# Sensor_LinearCCD.net
KiCad netlist of a schematic drawn in EAGLE
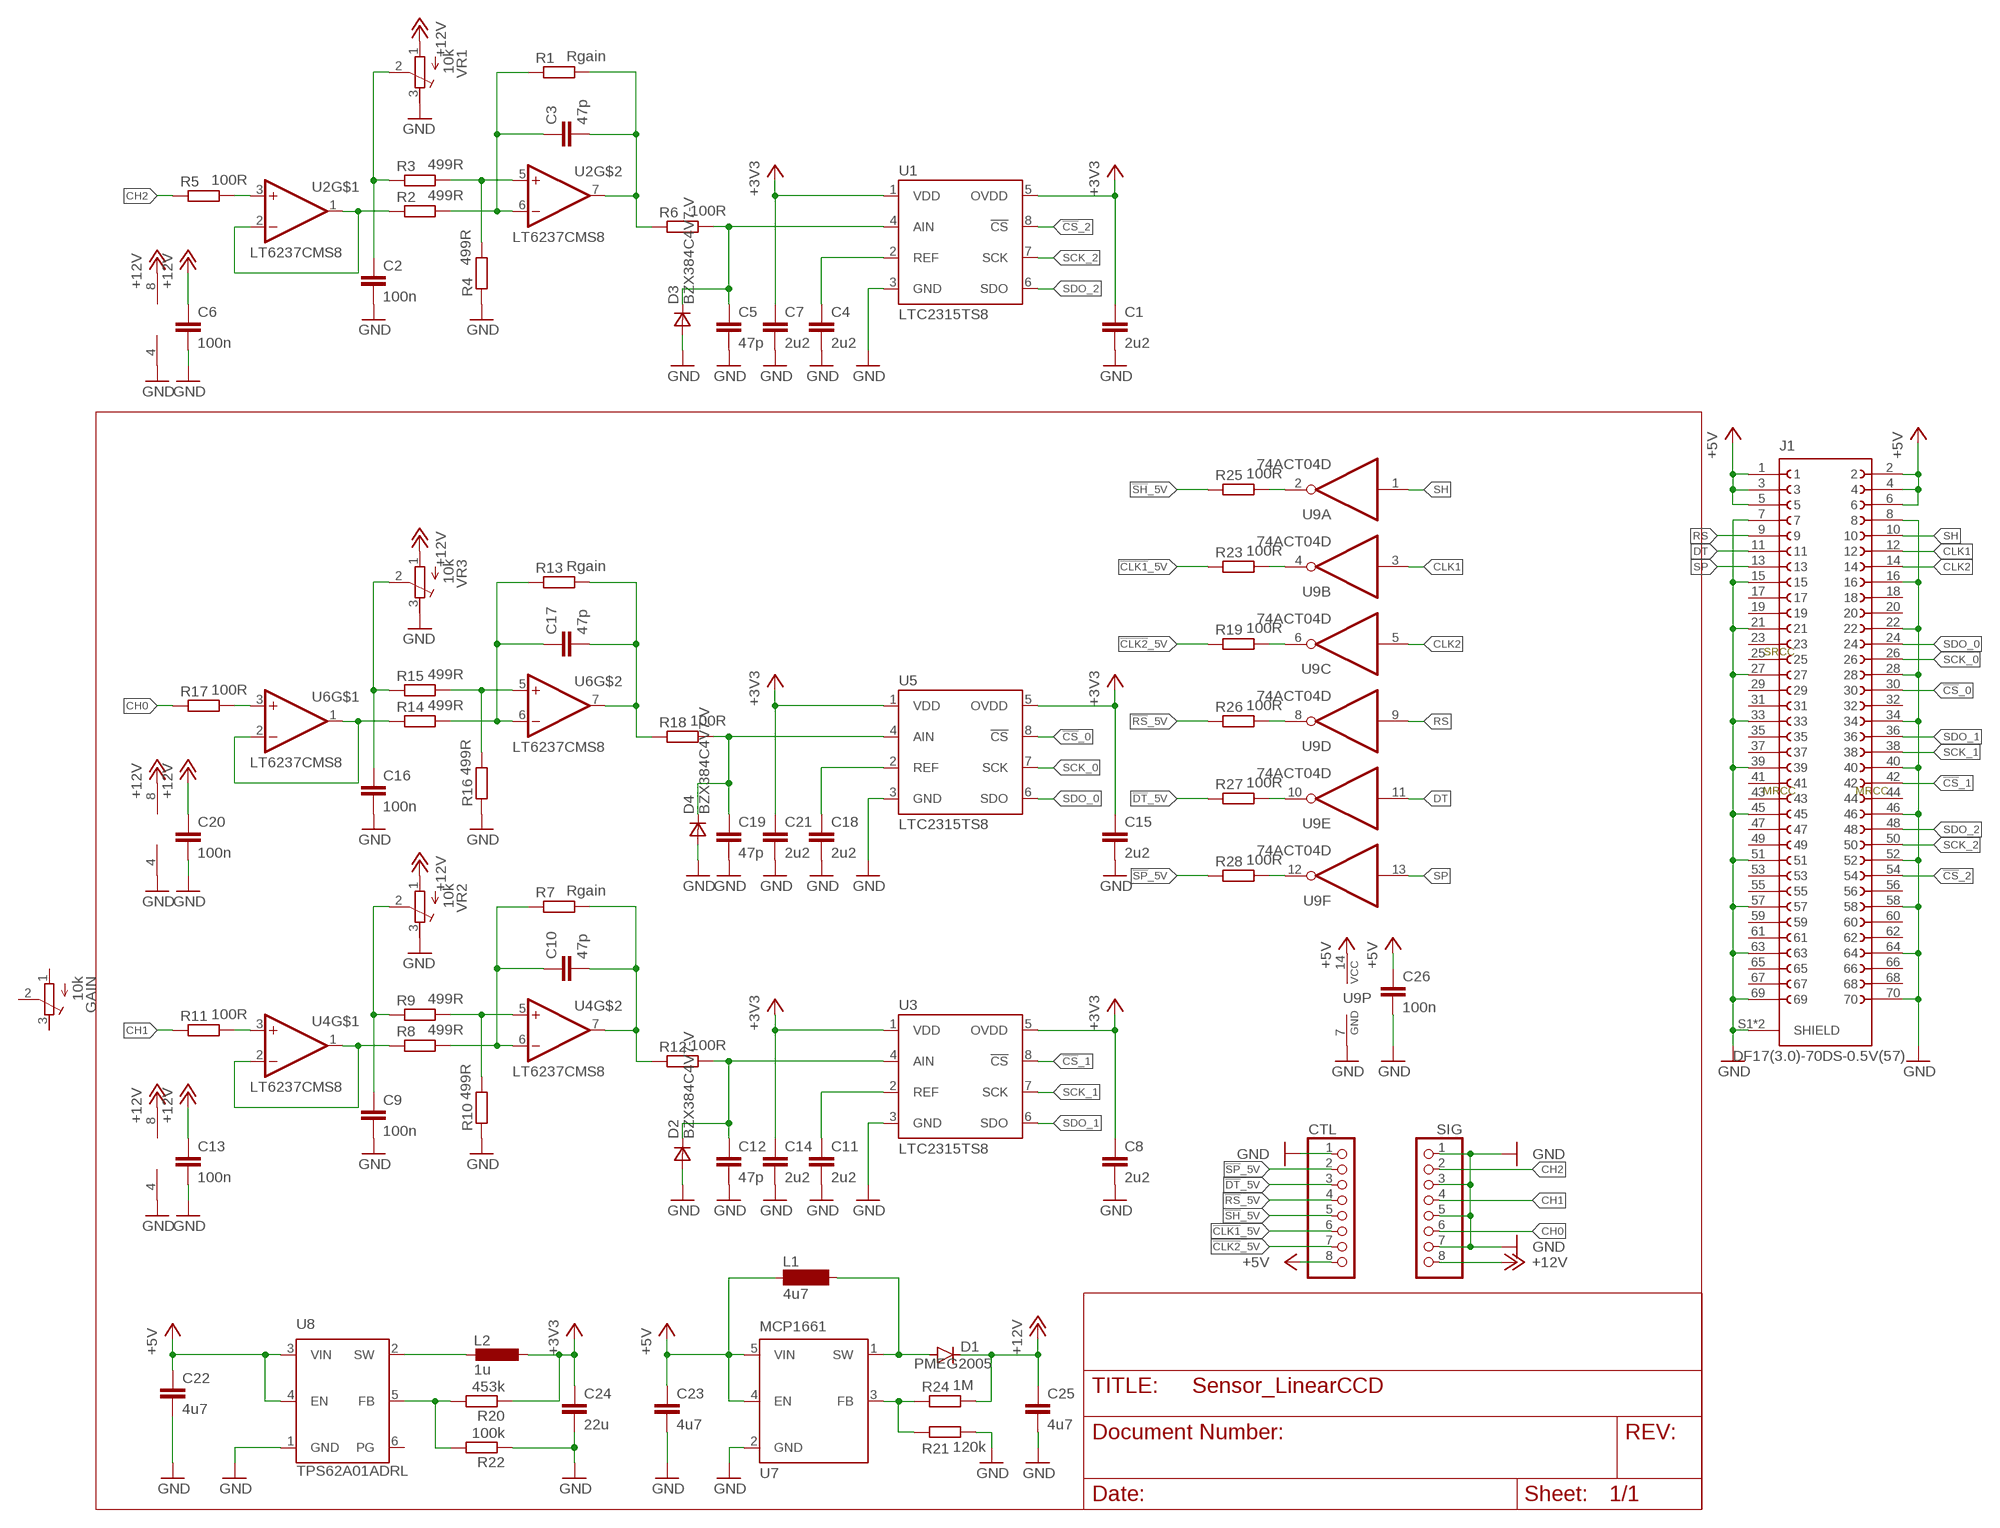
[diagram p0: schematic, sheet 1]

(export (version "E")
  (design (tool "Eeschema 10.0.6"))
  (components
    (comp (ref "C1")
      (value "2u2")
      (footprint "eagle-import:C0603")
      (libsource (lib "eagle-import") (part "C-EUC0603"))
    )
    (comp (ref "C2")
      (value "100n")
      (footprint "eagle-import:C0402")
      (libsource (lib "eagle-import") (part "rcl_334_C-EUC0402"))
    )
    (comp (ref "C3")
      (value "47p")
      (footprint "eagle-import:C0402")
      (libsource (lib "eagle-import") (part "rcl_334_C-EUC0402"))
    )
    (comp (ref "C4")
      (value "2u2")
      (footprint "eagle-import:C0603")
      (libsource (lib "eagle-import") (part "C-EUC0603"))
    )
    (comp (ref "C5")
      (value "47p")
      (footprint "eagle-import:C0402")
      (libsource (lib "eagle-import") (part "rcl_334_C-EUC0402"))
    )
    (comp (ref "C6")
      (value "100n")
      (footprint "eagle-import:C0402")
      (libsource (lib "eagle-import") (part "rcl_334_C-EUC0402"))
    )
    (comp (ref "C7")
      (value "2u2")
      (footprint "eagle-import:C0603")
      (libsource (lib "eagle-import") (part "C-EUC0603"))
    )
    (comp (ref "C8")
      (value "2u2")
      (footprint "eagle-import:C0603")
      (libsource (lib "eagle-import") (part "C-EUC0603"))
    )
    (comp (ref "C9")
      (value "100n")
      (footprint "eagle-import:C0402")
      (libsource (lib "eagle-import") (part "rcl_334_C-EUC0402"))
    )
    (comp (ref "C10")
      (value "47p")
      (footprint "eagle-import:C0402")
      (libsource (lib "eagle-import") (part "rcl_334_C-EUC0402"))
    )
    (comp (ref "C11")
      (value "2u2")
      (footprint "eagle-import:C0603")
      (libsource (lib "eagle-import") (part "C-EUC0603"))
    )
    (comp (ref "C12")
      (value "47p")
      (footprint "eagle-import:C0402")
      (libsource (lib "eagle-import") (part "rcl_334_C-EUC0402"))
    )
    (comp (ref "C13")
      (value "100n")
      (footprint "eagle-import:C0402")
      (libsource (lib "eagle-import") (part "rcl_334_C-EUC0402"))
    )
    (comp (ref "C14")
      (value "2u2")
      (footprint "eagle-import:C0603")
      (libsource (lib "eagle-import") (part "C-EUC0603"))
    )
    (comp (ref "C15")
      (value "2u2")
      (footprint "eagle-import:C0603")
      (libsource (lib "eagle-import") (part "C-EUC0603"))
    )
    (comp (ref "C16")
      (value "100n")
      (footprint "eagle-import:C0402")
      (libsource (lib "eagle-import") (part "rcl_334_C-EUC0402"))
    )
    (comp (ref "C17")
      (value "47p")
      (footprint "eagle-import:C0402")
      (libsource (lib "eagle-import") (part "rcl_334_C-EUC0402"))
    )
    (comp (ref "C18")
      (value "2u2")
      (footprint "eagle-import:C0603")
      (libsource (lib "eagle-import") (part "C-EUC0603"))
    )
    (comp (ref "C19")
      (value "47p")
      (footprint "eagle-import:C0402")
      (libsource (lib "eagle-import") (part "rcl_334_C-EUC0402"))
    )
    (comp (ref "C20")
      (value "100n")
      (footprint "eagle-import:C0402")
      (libsource (lib "eagle-import") (part "rcl_334_C-EUC0402"))
    )
    (comp (ref "C21")
      (value "2u2")
      (footprint "eagle-import:C0603")
      (libsource (lib "eagle-import") (part "C-EUC0603"))
    )
    (comp (ref "C22")
      (value "4u7")
      (footprint "eagle-import:C0603")
      (libsource (lib "eagle-import") (part "C-EUC0603"))
    )
    (comp (ref "C23")
      (value "4u7")
      (footprint "eagle-import:C0603")
      (libsource (lib "eagle-import") (part "C-EUC0603"))
    )
    (comp (ref "C24")
      (value "22u")
      (footprint "eagle-import:C0603")
      (libsource (lib "eagle-import") (part "C-EUC0603"))
    )
    (comp (ref "C25")
      (value "4u7")
      (footprint "eagle-import:C0603")
      (libsource (lib "eagle-import") (part "C-EUC0603"))
    )
    (comp (ref "C26")
      (value "100n")
      (footprint "eagle-import:C0402")
      (libsource (lib "eagle-import") (part "rcl_334_C-EUC0402"))
    )
    (comp (ref "CTL")
      (value "PINHD-1X8_2.00")
      (footprint "eagle-import:1X08M")
      (libsource (lib "eagle-import") (part "PINHD-1X8_2.00"))
    )
    (comp (ref "D1")
      (value "PMEG2005")
      (footprint "eagle-import:SOD123")
      (libsource (lib "eagle-import") (part "DIODE-SOD123"))
    )
    (comp (ref "D2")
      (value "BZX384C4V7-V")
      (footprint "eagle-import:SOD323")
      (fields (field (name "MPN") "CDSOD323-T05C"))
      (libsource (lib "eagle-import") (part "DSOD323"))
    )
    (comp (ref "D3")
      (value "BZX384C4V7-V")
      (footprint "eagle-import:SOD323")
      (fields (field (name "MPN") "CDSOD323-T05C"))
      (libsource (lib "eagle-import") (part "DSOD323"))
    )
    (comp (ref "D4")
      (value "BZX384C4V7-V")
      (footprint "eagle-import:SOD323")
      (fields (field (name "MPN") "CDSOD323-T05C"))
      (libsource (lib "eagle-import") (part "DSOD323"))
    )
    (comp (ref "GAIN")
      (value "10k")
      (footprint "eagle-import:RTRIM3224J")
      (libsource (lib "eagle-import") (part "R-TRIMM3224J"))
    )
    (comp (ref "J1")
      (value "DF17(3.0)-70DS-0.5V(57)")
      (footprint "eagle-import:DF17(3.0)-70DS-0.5V(57)")
      (libsource (lib "eagle-import") (part "DF17(3.0)-70DS-0.5V(57)"))
    )
    (comp (ref "L1")
      (value "4u7")
      (footprint "eagle-import:L4012")
      (libsource (lib "eagle-import") (part "L4012"))
    )
    (comp (ref "L2")
      (value "1u")
      (footprint "eagle-import:L1008")
      (fields (field (name "MPN") "LQM2HPN1R0MG0L"))
      (libsource (lib "eagle-import") (part "L-EU1008"))
    )
    (comp (ref "R1")
      (value "Rgain")
      (footprint "eagle-import:R0402")
      (libsource (lib "eagle-import") (part "R-EU_R0402"))
    )
    (comp (ref "R2")
      (value "499R")
      (footprint "eagle-import:R0402")
      (libsource (lib "eagle-import") (part "R-EU_R0402"))
    )
    (comp (ref "R3")
      (value "499R")
      (footprint "eagle-import:R0402")
      (libsource (lib "eagle-import") (part "R-EU_R0402"))
    )
    (comp (ref "R4")
      (value "499R")
      (footprint "eagle-import:R0402")
      (libsource (lib "eagle-import") (part "R-EU_R0402"))
    )
    (comp (ref "R5")
      (value "100R")
      (footprint "eagle-import:R0402")
      (libsource (lib "eagle-import") (part "R-EU_R0402"))
    )
    (comp (ref "R6")
      (value "100R")
      (footprint "eagle-import:R0402")
      (libsource (lib "eagle-import") (part "R-EU_R0402"))
    )
    (comp (ref "R7")
      (value "Rgain")
      (footprint "eagle-import:R0402")
      (libsource (lib "eagle-import") (part "R-EU_R0402"))
    )
    (comp (ref "R8")
      (value "499R")
      (footprint "eagle-import:R0402")
      (libsource (lib "eagle-import") (part "R-EU_R0402"))
    )
    (comp (ref "R9")
      (value "499R")
      (footprint "eagle-import:R0402")
      (libsource (lib "eagle-import") (part "R-EU_R0402"))
    )
    (comp (ref "R10")
      (value "499R")
      (footprint "eagle-import:R0402")
      (libsource (lib "eagle-import") (part "R-EU_R0402"))
    )
    (comp (ref "R11")
      (value "100R")
      (footprint "eagle-import:R0402")
      (libsource (lib "eagle-import") (part "R-EU_R0402"))
    )
    (comp (ref "R12")
      (value "100R")
      (footprint "eagle-import:R0402")
      (libsource (lib "eagle-import") (part "R-EU_R0402"))
    )
    (comp (ref "R13")
      (value "Rgain")
      (footprint "eagle-import:R0402")
      (libsource (lib "eagle-import") (part "R-EU_R0402"))
    )
    (comp (ref "R14")
      (value "499R")
      (footprint "eagle-import:R0402")
      (libsource (lib "eagle-import") (part "R-EU_R0402"))
    )
    (comp (ref "R15")
      (value "499R")
      (footprint "eagle-import:R0402")
      (libsource (lib "eagle-import") (part "R-EU_R0402"))
    )
    (comp (ref "R16")
      (value "499R")
      (footprint "eagle-import:R0402")
      (libsource (lib "eagle-import") (part "R-EU_R0402"))
    )
    (comp (ref "R17")
      (value "100R")
      (footprint "eagle-import:R0402")
      (libsource (lib "eagle-import") (part "R-EU_R0402"))
    )
    (comp (ref "R18")
      (value "100R")
      (footprint "eagle-import:R0402")
      (libsource (lib "eagle-import") (part "R-EU_R0402"))
    )
    (comp (ref "R19")
      (value "100R")
      (footprint "eagle-import:R0402")
      (libsource (lib "eagle-import") (part "R-EU_R0402"))
    )
    (comp (ref "R20")
      (value "453k")
      (footprint "eagle-import:R0402")
      (libsource (lib "eagle-import") (part "R-EU_R0402"))
    )
    (comp (ref "R21")
      (value "120k")
      (footprint "eagle-import:R0402")
      (libsource (lib "eagle-import") (part "R-EU_R0402"))
    )
    (comp (ref "R22")
      (value "100k")
      (footprint "eagle-import:R0402")
      (libsource (lib "eagle-import") (part "R-EU_R0402"))
    )
    (comp (ref "R23")
      (value "100R")
      (footprint "eagle-import:R0402")
      (libsource (lib "eagle-import") (part "R-EU_R0402"))
    )
    (comp (ref "R24")
      (value "1M")
      (footprint "eagle-import:R0402")
      (libsource (lib "eagle-import") (part "R-EU_R0402"))
    )
    (comp (ref "R25")
      (value "100R")
      (footprint "eagle-import:R0402")
      (libsource (lib "eagle-import") (part "R-EU_R0402"))
    )
    (comp (ref "R26")
      (value "100R")
      (footprint "eagle-import:R0402")
      (libsource (lib "eagle-import") (part "R-EU_R0402"))
    )
    (comp (ref "R27")
      (value "100R")
      (footprint "eagle-import:R0402")
      (libsource (lib "eagle-import") (part "R-EU_R0402"))
    )
    (comp (ref "R28")
      (value "100R")
      (footprint "eagle-import:R0402")
      (libsource (lib "eagle-import") (part "R-EU_R0402"))
    )
    (comp (ref "SIG")
      (value "PINHD-1X8_2.00")
      (footprint "eagle-import:1X08M")
      (libsource (lib "eagle-import") (part "PINHD-1X8_2.00"))
    )
    (comp (ref "U1")
      (value "LTC2315TS8")
      (footprint "eagle-import:SOT23-8L")
      (libsource (lib "eagle-import") (part "LTC2315TS8"))
    )
    (comp (ref "U2")
      (value "LT6237CMS8")
      (footprint "eagle-import:MSOP08")
      (libsource (lib "eagle-import") (part "LT6237CMS8"))
    )
    (comp (ref "U3")
      (value "LTC2315TS8")
      (footprint "eagle-import:SOT23-8L")
      (libsource (lib "eagle-import") (part "LTC2315TS8"))
    )
    (comp (ref "U4")
      (value "LT6237CMS8")
      (footprint "eagle-import:MSOP08")
      (libsource (lib "eagle-import") (part "LT6237CMS8"))
    )
    (comp (ref "U5")
      (value "LTC2315TS8")
      (footprint "eagle-import:SOT23-8L")
      (libsource (lib "eagle-import") (part "LTC2315TS8"))
    )
    (comp (ref "U6")
      (value "LT6237CMS8")
      (footprint "eagle-import:MSOP08")
      (libsource (lib "eagle-import") (part "LT6237CMS8"))
    )
    (comp (ref "U7")
      (value "MCP1661")
      (footprint "eagle-import:SOT23-5L")
      (libsource (lib "eagle-import") (part "MCP1661"))
    )
    (comp (ref "U8")
      (value "TPS62A01ADRL")
      (footprint "eagle-import:SOTFL50P160X60-6N")
      (fields (field (name "MANUFACTURER_PART_NUMBER") "TPS62A01ADRLR"))
      (libsource (lib "eagle-import") (part "TPS62A01ADRL"))
    )
    (comp (ref "U9")
      (value "74ACT04D")
      (footprint "eagle-import:SO14")
      (libsource (lib "eagle-import") (part "7404DACT"))
    )
    (comp (ref "VR1")
      (value "10k")
      (footprint "eagle-import:RTRIM3224J")
      (libsource (lib "eagle-import") (part "R-TRIMM3224J"))
    )
    (comp (ref "VR2")
      (value "10k")
      (footprint "eagle-import:RTRIM3224J")
      (libsource (lib "eagle-import") (part "R-TRIMM3224J"))
    )
    (comp (ref "VR3")
      (value "10k")
      (footprint "eagle-import:RTRIM3224J")
      (libsource (lib "eagle-import") (part "R-TRIMM3224J"))
    )
  )
  (nets
    (net (code "1") (name "+3V3") (class "Default")
      (node (ref "C1") (pin "1") (pinfunction "1_1") (pintype "passive"))
      (node (ref "C14") (pin "1") (pinfunction "1_1") (pintype "passive"))
      (node (ref "C15") (pin "1") (pinfunction "1_1") (pintype "passive"))
      (node (ref "C21") (pin "1") (pinfunction "1_1") (pintype "passive"))
      (node (ref "C24") (pin "1") (pinfunction "1_1") (pintype "passive"))
      (node (ref "C7") (pin "1") (pinfunction "1_1") (pintype "passive"))
      (node (ref "C8") (pin "1") (pinfunction "1_1") (pintype "passive"))
      (node (ref "L2") (pin "1") (pinfunction "1_1") (pintype "passive"))
      (node (ref "R20") (pin "1") (pinfunction "1_1") (pintype "passive"))
      (node (ref "U1") (pin "1") (pinfunction "VDD_1") (pintype "power_in"))
      (node (ref "U1") (pin "5") (pinfunction "OVDD_5") (pintype "power_in"))
      (node (ref "U3") (pin "1") (pinfunction "VDD_1") (pintype "power_in"))
      (node (ref "U3") (pin "5") (pinfunction "OVDD_5") (pintype "power_in"))
      (node (ref "U5") (pin "1") (pinfunction "VDD_1") (pintype "power_in"))
      (node (ref "U5") (pin "5") (pinfunction "OVDD_5") (pintype "power_in"))
    )
    (net (code "2") (name "+5V") (class "Default")
      (node (ref "C22") (pin "1") (pinfunction "1_1") (pintype "passive"))
      (node (ref "C23") (pin "1") (pinfunction "1_1") (pintype "passive"))
      (node (ref "C26") (pin "1") (pinfunction "1_1") (pintype "passive"))
      (node (ref "CTL") (pin "8") (pinfunction "8_8") (pintype "passive"))
      (node (ref "J1") (pin "1") (pinfunction "1_1") (pintype "passive"))
      (node (ref "J1") (pin "2") (pinfunction "2_2") (pintype "passive"))
      (node (ref "J1") (pin "3") (pinfunction "3_3") (pintype "passive"))
      (node (ref "J1") (pin "4") (pinfunction "4_4") (pintype "passive"))
      (node (ref "J1") (pin "5") (pinfunction "5_5") (pintype "passive"))
      (node (ref "J1") (pin "6") (pinfunction "6_6") (pintype "passive"))
      (node (ref "L1") (pin "1") (pinfunction "1_1") (pintype "passive"))
      (node (ref "U7") (pin "4") (pinfunction "EN_4") (pintype "input"))
      (node (ref "U7") (pin "5") (pinfunction "VIN_5") (pintype "power_in"))
      (node (ref "U8") (pin "3") (pinfunction "VIN_3") (pintype "bidirectional"))
      (node (ref "U8") (pin "4") (pinfunction "EN_4") (pintype "bidirectional"))
      (node (ref "U9") (pin "14") (pinfunction "VCC_14") (pintype "power_in"))
    )
    (net (code "3") (name "+12V") (class "Default")
      (node (ref "C13") (pin "1") (pinfunction "1_1") (pintype "passive"))
      (node (ref "C20") (pin "1") (pinfunction "1_1") (pintype "passive"))
      (node (ref "C25") (pin "1") (pinfunction "1_1") (pintype "passive"))
      (node (ref "C6") (pin "1") (pinfunction "1_1") (pintype "passive"))
      (node (ref "D1") (pin "C") (pinfunction "C_C") (pintype "passive"))
      (node (ref "R24") (pin "2") (pinfunction "2_2") (pintype "passive"))
      (node (ref "SIG") (pin "8") (pinfunction "8_8") (pintype "passive"))
      (node (ref "U2") (pin "8") (pinfunction "V+_8") (pintype "power_in"))
      (node (ref "U4") (pin "8") (pinfunction "V+_8") (pintype "power_in"))
      (node (ref "U6") (pin "8") (pinfunction "V+_8") (pintype "power_in"))
      (node (ref "VR1") (pin "1") (pinfunction "A_1") (pintype "passive"))
      (node (ref "VR2") (pin "1") (pinfunction "A_1") (pintype "passive"))
      (node (ref "VR3") (pin "1") (pinfunction "A_1") (pintype "passive"))
    )
    (net (code "4") (name "/~{CLK1}_5V") (class "Default")
      (node (ref "CTL") (pin "6") (pinfunction "6_6") (pintype "passive"))
      (node (ref "R23") (pin "1") (pinfunction "1_1") (pintype "passive"))
    )
    (net (code "5") (name "/~{CLK2}_5V") (class "Default")
      (node (ref "CTL") (pin "7") (pinfunction "7_7") (pintype "passive"))
      (node (ref "R19") (pin "1") (pinfunction "1_1") (pintype "passive"))
    )
    (net (code "6") (name "/~{CS}_0") (class "Default")
      (node (ref "J1") (pin "30") (pinfunction "30_30") (pintype "passive"))
      (node (ref "U5") (pin "8") (pinfunction "~{CS}_8") (pintype "input"))
    )
    (net (code "7") (name "/~{CS}_1") (class "Default")
      (node (ref "J1") (pin "42") (pinfunction "42_42") (pintype "passive"))
      (node (ref "U3") (pin "8") (pinfunction "~{CS}_8") (pintype "input"))
    )
    (net (code "8") (name "/~{CS}_2") (class "Default")
      (node (ref "J1") (pin "54") (pinfunction "54_54") (pintype "passive"))
      (node (ref "U1") (pin "8") (pinfunction "~{CS}_8") (pintype "input"))
    )
    (net (code "9") (name "/~{DT}_5V") (class "Default")
      (node (ref "CTL") (pin "3") (pinfunction "3_3") (pintype "passive"))
      (node (ref "R27") (pin "1") (pinfunction "1_1") (pintype "passive"))
    )
    (net (code "10") (name "/~{RS}_5V") (class "Default")
      (node (ref "CTL") (pin "4") (pinfunction "4_4") (pintype "passive"))
      (node (ref "R26") (pin "1") (pinfunction "1_1") (pintype "passive"))
    )
    (net (code "11") (name "/~{SH}_5V") (class "Default")
      (node (ref "CTL") (pin "5") (pinfunction "5_5") (pintype "passive"))
      (node (ref "R25") (pin "1") (pinfunction "1_1") (pintype "passive"))
    )
    (net (code "12") (name "/~{SP}_5V") (class "Default")
      (node (ref "CTL") (pin "2") (pinfunction "2_2") (pintype "passive"))
      (node (ref "R28") (pin "1") (pinfunction "1_1") (pintype "passive"))
    )
    (net (code "13") (name "CH0") (class "Default")
      (node (ref "R17") (pin "1") (pinfunction "1_1") (pintype "passive"))
      (node (ref "SIG") (pin "6") (pinfunction "6_6") (pintype "passive"))
    )
    (net (code "14") (name "CH1") (class "Default")
      (node (ref "R11") (pin "1") (pinfunction "1_1") (pintype "passive"))
      (node (ref "SIG") (pin "4") (pinfunction "4_4") (pintype "passive"))
    )
    (net (code "15") (name "CH2") (class "Default")
      (node (ref "R5") (pin "1") (pinfunction "1_1") (pintype "passive"))
      (node (ref "SIG") (pin "2") (pinfunction "2_2") (pintype "passive"))
    )
    (net (code "16") (name "CLK1") (class "Default")
      (node (ref "J1") (pin "12") (pinfunction "12_12") (pintype "passive"))
      (node (ref "U9") (pin "3") (pinfunction "I_3") (pintype "input"))
    )
    (net (code "17") (name "CLK2") (class "Default")
      (node (ref "J1") (pin "14") (pinfunction "14_14") (pintype "passive"))
      (node (ref "U9") (pin "5") (pinfunction "I_5") (pintype "input"))
    )
    (net (code "18") (name "DT") (class "Default")
      (node (ref "J1") (pin "11") (pinfunction "11_11") (pintype "passive"))
      (node (ref "U9") (pin "11") (pinfunction "I_11") (pintype "input"))
    )
    (net (code "19") (name "GND") (class "Default")
      (node (ref "C1") (pin "2") (pinfunction "2_2") (pintype "passive"))
      (node (ref "C11") (pin "2") (pinfunction "2_2") (pintype "passive"))
      (node (ref "C12") (pin "2") (pinfunction "2_2") (pintype "passive"))
      (node (ref "C13") (pin "2") (pinfunction "2_2") (pintype "passive"))
      (node (ref "C14") (pin "2") (pinfunction "2_2") (pintype "passive"))
      (node (ref "C15") (pin "2") (pinfunction "2_2") (pintype "passive"))
      (node (ref "C16") (pin "2") (pinfunction "2_2") (pintype "passive"))
      (node (ref "C18") (pin "2") (pinfunction "2_2") (pintype "passive"))
      (node (ref "C19") (pin "2") (pinfunction "2_2") (pintype "passive"))
      (node (ref "C2") (pin "2") (pinfunction "2_2") (pintype "passive"))
      (node (ref "C20") (pin "2") (pinfunction "2_2") (pintype "passive"))
      (node (ref "C21") (pin "2") (pinfunction "2_2") (pintype "passive"))
      (node (ref "C22") (pin "2") (pinfunction "2_2") (pintype "passive"))
      (node (ref "C23") (pin "2") (pinfunction "2_2") (pintype "passive"))
      (node (ref "C24") (pin "2") (pinfunction "2_2") (pintype "passive"))
      (node (ref "C25") (pin "2") (pinfunction "2_2") (pintype "passive"))
      (node (ref "C26") (pin "2") (pinfunction "2_2") (pintype "passive"))
      (node (ref "C4") (pin "2") (pinfunction "2_2") (pintype "passive"))
      (node (ref "C5") (pin "2") (pinfunction "2_2") (pintype "passive"))
      (node (ref "C6") (pin "2") (pinfunction "2_2") (pintype "passive"))
      (node (ref "C7") (pin "2") (pinfunction "2_2") (pintype "passive"))
      (node (ref "C8") (pin "2") (pinfunction "2_2") (pintype "passive"))
      (node (ref "C9") (pin "2") (pinfunction "2_2") (pintype "passive"))
      (node (ref "CTL") (pin "1") (pinfunction "1_1") (pintype "passive"))
      (node (ref "D2") (pin "2") (pinfunction "A_2") (pintype "passive"))
      (node (ref "D3") (pin "2") (pinfunction "A_2") (pintype "passive"))
      (node (ref "D4") (pin "2") (pinfunction "A_2") (pintype "passive"))
      (node (ref "J1") (pin "15") (pinfunction "15_15") (pintype "passive"))
      (node (ref "J1") (pin "16") (pinfunction "16_16") (pintype "passive"))
      (node (ref "J1") (pin "21") (pinfunction "21_21") (pintype "passive"))
      (node (ref "J1") (pin "22") (pinfunction "22_22") (pintype "passive"))
      (node (ref "J1") (pin "27") (pinfunction "27_27") (pintype "passive"))
      (node (ref "J1") (pin "28") (pinfunction "28_28") (pintype "passive"))
      (node (ref "J1") (pin "33") (pinfunction "33_33") (pintype "passive"))
      (node (ref "J1") (pin "34") (pinfunction "34_34") (pintype "passive"))
      (node (ref "J1") (pin "39") (pinfunction "39_39") (pintype "passive"))
      (node (ref "J1") (pin "40") (pinfunction "40_40") (pintype "passive"))
      (node (ref "J1") (pin "45") (pinfunction "45_45") (pintype "passive"))
      (node (ref "J1") (pin "46") (pinfunction "46_46") (pintype "passive"))
      (node (ref "J1") (pin "51") (pinfunction "51_51") (pintype "passive"))
      (node (ref "J1") (pin "52") (pinfunction "52_52") (pintype "passive"))
      (node (ref "J1") (pin "57") (pinfunction "57_57") (pintype "passive"))
      (node (ref "J1") (pin "58") (pinfunction "58_58") (pintype "passive"))
      (node (ref "J1") (pin "63") (pinfunction "63_63") (pintype "passive"))
      (node (ref "J1") (pin "64") (pinfunction "64_64") (pintype "passive"))
      (node (ref "J1") (pin "69") (pinfunction "69_69") (pintype "passive"))
      (node (ref "J1") (pin "7") (pinfunction "7_7") (pintype "passive"))
      (node (ref "J1") (pin "70") (pinfunction "70_70") (pintype "passive"))
      (node (ref "J1") (pin "8") (pinfunction "8_8") (pintype "passive"))
      (node (ref "J1") (pin "S1") (pinfunction "SHIELD_S1") (pintype "passive"))
      (node (ref "J1") (pin "S2") (pinfunction "SHIELD_S2") (pintype "passive"))
      (node (ref "R10") (pin "1") (pinfunction "1_1") (pintype "passive"))
      (node (ref "R16") (pin "1") (pinfunction "1_1") (pintype "passive"))
      (node (ref "R21") (pin "2") (pinfunction "2_2") (pintype "passive"))
      (node (ref "R22") (pin "1") (pinfunction "1_1") (pintype "passive"))
      (node (ref "R4") (pin "1") (pinfunction "1_1") (pintype "passive"))
      (node (ref "SIG") (pin "1") (pinfunction "1_1") (pintype "passive"))
      (node (ref "SIG") (pin "3") (pinfunction "3_3") (pintype "passive"))
      (node (ref "SIG") (pin "5") (pinfunction "5_5") (pintype "passive"))
      (node (ref "SIG") (pin "7") (pinfunction "7_7") (pintype "passive"))
      (node (ref "U1") (pin "3") (pinfunction "GND_3") (pintype "power_in"))
      (node (ref "U2") (pin "4") (pinfunction "V-_4") (pintype "power_in"))
      (node (ref "U3") (pin "3") (pinfunction "GND_3") (pintype "power_in"))
      (node (ref "U4") (pin "4") (pinfunction "V-_4") (pintype "power_in"))
      (node (ref "U5") (pin "3") (pinfunction "GND_3") (pintype "power_in"))
      (node (ref "U6") (pin "4") (pinfunction "V-_4") (pintype "power_in"))
      (node (ref "U7") (pin "2") (pinfunction "GND_2") (pintype "power_in"))
      (node (ref "U8") (pin "1") (pinfunction "GND_1") (pintype "bidirectional"))
      (node (ref "U9") (pin "7") (pinfunction "GND_7") (pintype "power_in"))
      (node (ref "VR1") (pin "3") (pinfunction "E_3") (pintype "passive"))
      (node (ref "VR2") (pin "3") (pinfunction "E_3") (pintype "passive"))
      (node (ref "VR3") (pin "3") (pinfunction "E_3") (pintype "passive"))
    )
    (net (code "20") (name "Net-(D2-C)") (class "Default")
      (node (ref "C12") (pin "1") (pinfunction "1_1") (pintype "passive"))
      (node (ref "D2") (pin "1") (pinfunction "C_1") (pintype "passive"))
      (node (ref "R12") (pin "2") (pinfunction "2_2") (pintype "passive"))
      (node (ref "U3") (pin "4") (pinfunction "AIN_4") (pintype "input"))
    )
    (net (code "21") (name "Net-(D3-C)") (class "Default")
      (node (ref "C5") (pin "1") (pinfunction "1_1") (pintype "passive"))
      (node (ref "D3") (pin "1") (pinfunction "C_1") (pintype "passive"))
      (node (ref "R6") (pin "2") (pinfunction "2_2") (pintype "passive"))
      (node (ref "U1") (pin "4") (pinfunction "AIN_4") (pintype "input"))
    )
    (net (code "22") (name "Net-(D4-C)") (class "Default")
      (node (ref "C19") (pin "1") (pinfunction "1_1") (pintype "passive"))
      (node (ref "D4") (pin "1") (pinfunction "C_1") (pintype "passive"))
      (node (ref "R18") (pin "2") (pinfunction "2_2") (pintype "passive"))
      (node (ref "U5") (pin "4") (pinfunction "AIN_4") (pintype "input"))
    )
    (net (code "23") (name "Net-(U1-REF)") (class "Default")
      (node (ref "C4") (pin "1") (pinfunction "1_1") (pintype "passive"))
      (node (ref "U1") (pin "2") (pinfunction "REF_2") (pintype "input"))
    )
    (net (code "24") (name "Net-(U2A-+IN)") (class "Default")
      (node (ref "R5") (pin "2") (pinfunction "2_2") (pintype "passive"))
      (node (ref "U2") (pin "3") (pinfunction "+IN_3") (pintype "input"))
    )
    (net (code "25") (name "Net-(U2A--IN)") (class "Default")
      (node (ref "R2") (pin "1") (pinfunction "1_1") (pintype "passive"))
      (node (ref "U2") (pin "1") (pinfunction "OUT_1") (pintype "output"))
      (node (ref "U2") (pin "2") (pinfunction "-IN_2") (pintype "input"))
    )
    (net (code "26") (name "Net-(U2B-+IN)") (class "Default")
      (node (ref "R3") (pin "2") (pinfunction "2_2") (pintype "passive"))
      (node (ref "R4") (pin "2") (pinfunction "2_2") (pintype "passive"))
      (node (ref "U2") (pin "5") (pinfunction "+IN_5") (pintype "input"))
    )
    (net (code "27") (name "Net-(U2B--IN)") (class "Default")
      (node (ref "C3") (pin "1") (pinfunction "1_1") (pintype "passive"))
      (node (ref "R1") (pin "1") (pinfunction "1_1") (pintype "passive"))
      (node (ref "R2") (pin "2") (pinfunction "2_2") (pintype "passive"))
      (node (ref "U2") (pin "6") (pinfunction "-IN_6") (pintype "input"))
    )
    (net (code "28") (name "Net-(U2B-OUT)") (class "Default")
      (node (ref "C3") (pin "2") (pinfunction "2_2") (pintype "passive"))
      (node (ref "R1") (pin "2") (pinfunction "2_2") (pintype "passive"))
      (node (ref "R6") (pin "1") (pinfunction "1_1") (pintype "passive"))
      (node (ref "U2") (pin "7") (pinfunction "OUT_7") (pintype "output"))
    )
    (net (code "29") (name "Net-(U3-REF)") (class "Default")
      (node (ref "C11") (pin "1") (pinfunction "1_1") (pintype "passive"))
      (node (ref "U3") (pin "2") (pinfunction "REF_2") (pintype "input"))
    )
    (net (code "30") (name "Net-(U4A-+IN)") (class "Default")
      (node (ref "R11") (pin "2") (pinfunction "2_2") (pintype "passive"))
      (node (ref "U4") (pin "3") (pinfunction "+IN_3") (pintype "input"))
    )
    (net (code "31") (name "Net-(U4A--IN)") (class "Default")
      (node (ref "R8") (pin "1") (pinfunction "1_1") (pintype "passive"))
      (node (ref "U4") (pin "1") (pinfunction "OUT_1") (pintype "output"))
      (node (ref "U4") (pin "2") (pinfunction "-IN_2") (pintype "input"))
    )
    (net (code "32") (name "Net-(U4B-+IN)") (class "Default")
      (node (ref "R10") (pin "2") (pinfunction "2_2") (pintype "passive"))
      (node (ref "R9") (pin "2") (pinfunction "2_2") (pintype "passive"))
      (node (ref "U4") (pin "5") (pinfunction "+IN_5") (pintype "input"))
    )
    (net (code "33") (name "Net-(U4B--IN)") (class "Default")
      (node (ref "C10") (pin "1") (pinfunction "1_1") (pintype "passive"))
      (node (ref "R7") (pin "1") (pinfunction "1_1") (pintype "passive"))
      (node (ref "R8") (pin "2") (pinfunction "2_2") (pintype "passive"))
      (node (ref "U4") (pin "6") (pinfunction "-IN_6") (pintype "input"))
    )
    (net (code "34") (name "Net-(U4B-OUT)") (class "Default")
      (node (ref "C10") (pin "2") (pinfunction "2_2") (pintype "passive"))
      (node (ref "R12") (pin "1") (pinfunction "1_1") (pintype "passive"))
      (node (ref "R7") (pin "2") (pinfunction "2_2") (pintype "passive"))
      (node (ref "U4") (pin "7") (pinfunction "OUT_7") (pintype "output"))
    )
    (net (code "35") (name "Net-(U5-REF)") (class "Default")
      (node (ref "C18") (pin "1") (pinfunction "1_1") (pintype "passive"))
      (node (ref "U5") (pin "2") (pinfunction "REF_2") (pintype "input"))
    )
    (net (code "36") (name "Net-(U6A-+IN)") (class "Default")
      (node (ref "R17") (pin "2") (pinfunction "2_2") (pintype "passive"))
      (node (ref "U6") (pin "3") (pinfunction "+IN_3") (pintype "input"))
    )
    (net (code "37") (name "Net-(U6A--IN)") (class "Default")
      (node (ref "R14") (pin "1") (pinfunction "1_1") (pintype "passive"))
      (node (ref "U6") (pin "1") (pinfunction "OUT_1") (pintype "output"))
      (node (ref "U6") (pin "2") (pinfunction "-IN_2") (pintype "input"))
    )
    (net (code "38") (name "Net-(U6B-+IN)") (class "Default")
      (node (ref "R15") (pin "2") (pinfunction "2_2") (pintype "passive"))
      (node (ref "R16") (pin "2") (pinfunction "2_2") (pintype "passive"))
      (node (ref "U6") (pin "5") (pinfunction "+IN_5") (pintype "input"))
    )
    (net (code "39") (name "Net-(U6B--IN)") (class "Default")
      (node (ref "C17") (pin "1") (pinfunction "1_1") (pintype "passive"))
      (node (ref "R13") (pin "1") (pinfunction "1_1") (pintype "passive"))
      (node (ref "R14") (pin "2") (pinfunction "2_2") (pintype "passive"))
      (node (ref "U6") (pin "6") (pinfunction "-IN_6") (pintype "input"))
    )
    (net (code "40") (name "Net-(U6B-OUT)") (class "Default")
      (node (ref "C17") (pin "2") (pinfunction "2_2") (pintype "passive"))
      (node (ref "R13") (pin "2") (pinfunction "2_2") (pintype "passive"))
      (node (ref "R18") (pin "1") (pinfunction "1_1") (pintype "passive"))
      (node (ref "U6") (pin "7") (pinfunction "OUT_7") (pintype "output"))
    )
    (net (code "41") (name "Net-(U7-FB)") (class "Default")
      (node (ref "R21") (pin "1") (pinfunction "1_1") (pintype "passive"))
      (node (ref "R24") (pin "1") (pinfunction "1_1") (pintype "passive"))
      (node (ref "U7") (pin "3") (pinfunction "FB_3") (pintype "passive"))
    )
    (net (code "42") (name "Net-(U7-SW)") (class "Default")
      (node (ref "D1") (pin "A") (pinfunction "A_A") (pintype "passive"))
      (node (ref "L1") (pin "2") (pinfunction "2_2") (pintype "passive"))
      (node (ref "U7") (pin "1") (pinfunction "SW_1") (pintype "passive"))
    )
    (net (code "43") (name "Net-(U8-FB)") (class "Default")
      (node (ref "R20") (pin "2") (pinfunction "2_2") (pintype "passive"))
      (node (ref "R22") (pin "2") (pinfunction "2_2") (pintype "passive"))
      (node (ref "U8") (pin "5") (pinfunction "FB_5") (pintype "bidirectional"))
    )
    (net (code "44") (name "Net-(U8-SW)") (class "Default")
      (node (ref "L2") (pin "2") (pinfunction "2_2") (pintype "passive"))
      (node (ref "U8") (pin "2") (pinfunction "SW_2") (pintype "bidirectional"))
    )
    (net (code "45") (name "Net-(U9A-O)") (class "Default")
      (node (ref "R25") (pin "2") (pinfunction "2_2") (pintype "passive"))
      (node (ref "U9") (pin "2") (pinfunction "O_2") (pintype "output"))
    )
    (net (code "46") (name "Net-(U9B-O)") (class "Default")
      (node (ref "R23") (pin "2") (pinfunction "2_2") (pintype "passive"))
      (node (ref "U9") (pin "4") (pinfunction "O_4") (pintype "output"))
    )
    (net (code "47") (name "Net-(U9C-O)") (class "Default")
      (node (ref "R19") (pin "2") (pinfunction "2_2") (pintype "passive"))
      (node (ref "U9") (pin "6") (pinfunction "O_6") (pintype "output"))
    )
    (net (code "48") (name "Net-(U9D-O)") (class "Default")
      (node (ref "R26") (pin "2") (pinfunction "2_2") (pintype "passive"))
      (node (ref "U9") (pin "8") (pinfunction "O_8") (pintype "output"))
    )
    (net (code "49") (name "Net-(U9E-O)") (class "Default")
      (node (ref "R27") (pin "2") (pinfunction "2_2") (pintype "passive"))
      (node (ref "U9") (pin "10") (pinfunction "O_10") (pintype "output"))
    )
    (net (code "50") (name "Net-(U9F-O)") (class "Default")
      (node (ref "R28") (pin "2") (pinfunction "2_2") (pintype "passive"))
      (node (ref "U9") (pin "12") (pinfunction "O_12") (pintype "output"))
    )
    (net (code "51") (name "Net-(VR1-S)") (class "Default")
      (node (ref "C2") (pin "1") (pinfunction "1_1") (pintype "passive"))
      (node (ref "R3") (pin "1") (pinfunction "1_1") (pintype "passive"))
      (node (ref "VR1") (pin "2") (pinfunction "S_2") (pintype "passive"))
    )
    (net (code "52") (name "Net-(VR2-S)") (class "Default")
      (node (ref "C9") (pin "1") (pinfunction "1_1") (pintype "passive"))
      (node (ref "R9") (pin "1") (pinfunction "1_1") (pintype "passive"))
      (node (ref "VR2") (pin "2") (pinfunction "S_2") (pintype "passive"))
    )
    (net (code "53") (name "Net-(VR3-S)") (class "Default")
      (node (ref "C16") (pin "1") (pinfunction "1_1") (pintype "passive"))
      (node (ref "R15") (pin "1") (pinfunction "1_1") (pintype "passive"))
      (node (ref "VR3") (pin "2") (pinfunction "S_2") (pintype "passive"))
    )
    (net (code "54") (name "RS") (class "Default")
      (node (ref "J1") (pin "9") (pinfunction "9_9") (pintype "passive"))
      (node (ref "U9") (pin "9") (pinfunction "I_9") (pintype "input"))
    )
    (net (code "55") (name "SCK_0") (class "Default")
      (node (ref "J1") (pin "26") (pinfunction "26_26") (pintype "passive"))
      (node (ref "U5") (pin "7") (pinfunction "SCK_7") (pintype "input"))
    )
    (net (code "56") (name "SCK_1") (class "Default")
      (node (ref "J1") (pin "38") (pinfunction "38_38") (pintype "passive"))
      (node (ref "U3") (pin "7") (pinfunction "SCK_7") (pintype "input"))
    )
    (net (code "57") (name "SCK_2") (class "Default")
      (node (ref "J1") (pin "50") (pinfunction "50_50") (pintype "passive"))
      (node (ref "U1") (pin "7") (pinfunction "SCK_7") (pintype "input"))
    )
    (net (code "58") (name "SDO_0") (class "Default")
      (node (ref "J1") (pin "24") (pinfunction "24_24") (pintype "passive"))
      (node (ref "U5") (pin "6") (pinfunction "SDO_6") (pintype "output"))
    )
    (net (code "59") (name "SDO_1") (class "Default")
      (node (ref "J1") (pin "36") (pinfunction "36_36") (pintype "passive"))
      (node (ref "U3") (pin "6") (pinfunction "SDO_6") (pintype "output"))
    )
    (net (code "60") (name "SDO_2") (class "Default")
      (node (ref "J1") (pin "48") (pinfunction "48_48") (pintype "passive"))
      (node (ref "U1") (pin "6") (pinfunction "SDO_6") (pintype "output"))
    )
    (net (code "61") (name "SH") (class "Default")
      (node (ref "J1") (pin "10") (pinfunction "10_10") (pintype "passive"))
      (node (ref "U9") (pin "1") (pinfunction "I_1") (pintype "input"))
    )
    (net (code "62") (name "SP") (class "Default")
      (node (ref "J1") (pin "13") (pinfunction "13_13") (pintype "passive"))
      (node (ref "U9") (pin "13") (pinfunction "I_13") (pintype "input"))
    )
    (net (code "63") (name "unconnected-(GAIN-A-Pad1)") (class "Default")
      (node (ref "GAIN") (pin "1") (pinfunction "A_1") (pintype "passive"))
    )
    (net (code "64") (name "unconnected-(GAIN-E-Pad3)") (class "Default")
      (node (ref "GAIN") (pin "3") (pinfunction "E_3") (pintype "passive"))
    )
    (net (code "65") (name "unconnected-(GAIN-S-Pad2)") (class "Default")
      (node (ref "GAIN") (pin "2") (pinfunction "S_2") (pintype "passive"))
    )
    (net (code "66") (name "unconnected-(J1-Pad17)") (class "Default")
      (node (ref "J1") (pin "17") (pinfunction "17_17") (pintype "passive"))
    )
    (net (code "67") (name "unconnected-(J1-Pad18)") (class "Default")
      (node (ref "J1") (pin "18") (pinfunction "18_18") (pintype "passive"))
    )
    (net (code "68") (name "unconnected-(J1-Pad19)") (class "Default")
      (node (ref "J1") (pin "19") (pinfunction "19_19") (pintype "passive"))
    )
    (net (code "69") (name "unconnected-(J1-Pad20)") (class "Default")
      (node (ref "J1") (pin "20") (pinfunction "20_20") (pintype "passive"))
    )
    (net (code "70") (name "unconnected-(J1-Pad23)") (class "Default")
      (node (ref "J1") (pin "23") (pinfunction "23_23") (pintype "passive"))
    )
    (net (code "71") (name "unconnected-(J1-Pad25)") (class "Default")
      (node (ref "J1") (pin "25") (pinfunction "25_25") (pintype "passive"))
    )
    (net (code "72") (name "unconnected-(J1-Pad29)") (class "Default")
      (node (ref "J1") (pin "29") (pinfunction "29_29") (pintype "passive"))
    )
    (net (code "73") (name "unconnected-(J1-Pad31)") (class "Default")
      (node (ref "J1") (pin "31") (pinfunction "31_31") (pintype "passive"))
    )
    (net (code "74") (name "unconnected-(J1-Pad32)") (class "Default")
      (node (ref "J1") (pin "32") (pinfunction "32_32") (pintype "passive"))
    )
    (net (code "75") (name "unconnected-(J1-Pad35)") (class "Default")
      (node (ref "J1") (pin "35") (pinfunction "35_35") (pintype "passive"))
    )
    (net (code "76") (name "unconnected-(J1-Pad37)") (class "Default")
      (node (ref "J1") (pin "37") (pinfunction "37_37") (pintype "passive"))
    )
    (net (code "77") (name "unconnected-(J1-Pad41)") (class "Default")
      (node (ref "J1") (pin "41") (pinfunction "41_41") (pintype "passive"))
    )
    (net (code "78") (name "unconnected-(J1-Pad43)") (class "Default")
      (node (ref "J1") (pin "43") (pinfunction "43_43") (pintype "passive"))
    )
    (net (code "79") (name "unconnected-(J1-Pad44)") (class "Default")
      (node (ref "J1") (pin "44") (pinfunction "44_44") (pintype "passive"))
    )
    (net (code "80") (name "unconnected-(J1-Pad47)") (class "Default")
      (node (ref "J1") (pin "47") (pinfunction "47_47") (pintype "passive"))
    )
    (net (code "81") (name "unconnected-(J1-Pad49)") (class "Default")
      (node (ref "J1") (pin "49") (pinfunction "49_49") (pintype "passive"))
    )
    (net (code "82") (name "unconnected-(J1-Pad53)") (class "Default")
      (node (ref "J1") (pin "53") (pinfunction "53_53") (pintype "passive"))
    )
    (net (code "83") (name "unconnected-(J1-Pad55)") (class "Default")
      (node (ref "J1") (pin "55") (pinfunction "55_55") (pintype "passive"))
    )
    (net (code "84") (name "unconnected-(J1-Pad56)") (class "Default")
      (node (ref "J1") (pin "56") (pinfunction "56_56") (pintype "passive"))
    )
    (net (code "85") (name "unconnected-(J1-Pad59)") (class "Default")
      (node (ref "J1") (pin "59") (pinfunction "59_59") (pintype "passive"))
    )
    (net (code "86") (name "unconnected-(J1-Pad60)") (class "Default")
      (node (ref "J1") (pin "60") (pinfunction "60_60") (pintype "passive"))
    )
    (net (code "87") (name "unconnected-(J1-Pad61)") (class "Default")
      (node (ref "J1") (pin "61") (pinfunction "61_61") (pintype "passive"))
    )
    (net (code "88") (name "unconnected-(J1-Pad62)") (class "Default")
      (node (ref "J1") (pin "62") (pinfunction "62_62") (pintype "passive"))
    )
    (net (code "89") (name "unconnected-(J1-Pad65)") (class "Default")
      (node (ref "J1") (pin "65") (pinfunction "65_65") (pintype "passive"))
    )
    (net (code "90") (name "unconnected-(J1-Pad66)") (class "Default")
      (node (ref "J1") (pin "66") (pinfunction "66_66") (pintype "passive"))
    )
    (net (code "91") (name "unconnected-(J1-Pad67)") (class "Default")
      (node (ref "J1") (pin "67") (pinfunction "67_67") (pintype "passive"))
    )
    (net (code "92") (name "unconnected-(J1-Pad68)") (class "Default")
      (node (ref "J1") (pin "68") (pinfunction "68_68") (pintype "passive"))
    )
    (net (code "93") (name "unconnected-(U8-PG-Pad6)") (class "Default")
      (node (ref "U8") (pin "6") (pinfunction "PG_6") (pintype "bidirectional"))
    )
  )
)
